# IMU_v2.net
KiCad netlist of a schematic drawn in EAGLE
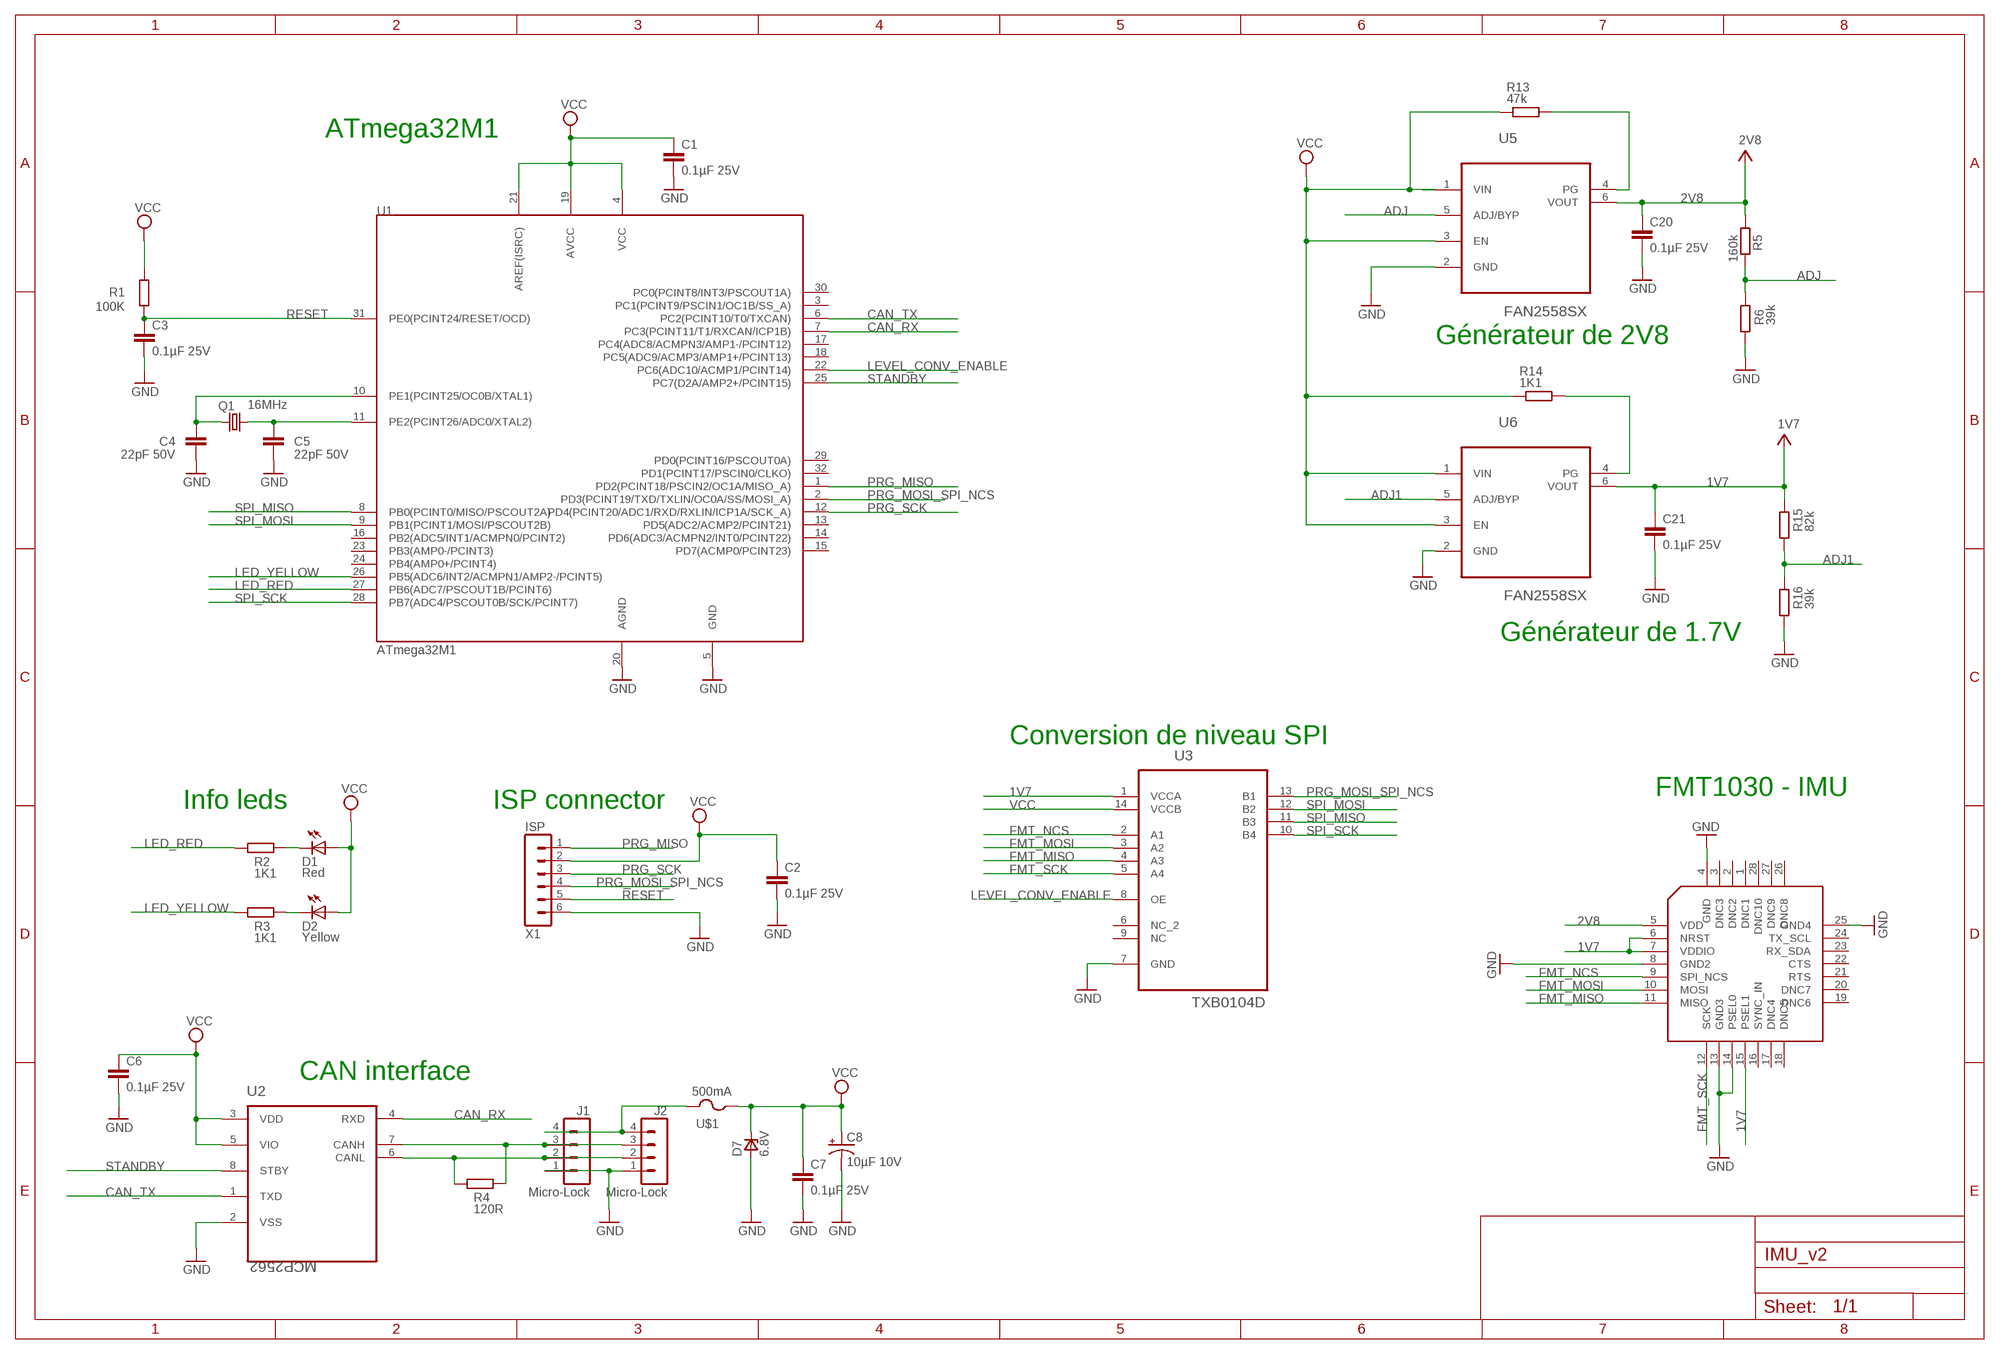
[diagram p0: schematic, sheet 1]

(export (version "E")
  (design (tool "Eeschema 10.0.6"))
  (components
    (comp (ref "C1")
      (value "0.1µF 25V")
      (footprint "eagle-import:C2012")
      (fields (field (name "MANUFACTURER") "AVX") (field (name "MPN") "08053C104KAT2A"))
      (libsource (lib "eagle-import") (part "CAPACITOR_NON_POL-0.1µF-25V(+-10%)(2012)"))
    )
    (comp (ref "C2")
      (value "0.1µF 25V")
      (footprint "eagle-import:C2012")
      (fields (field (name "MANUFACTURER") "AVX") (field (name "MPN") "08053C104KAT2A"))
      (libsource (lib "eagle-import") (part "CAPACITOR_NON_POL-0.1µF-25V(+-10%)(2012)"))
    )
    (comp (ref "C3")
      (value "0.1µF 25V")
      (footprint "eagle-import:C2012")
      (fields (field (name "MANUFACTURER") "AVX") (field (name "MPN") "08053C104KAT2A"))
      (libsource (lib "eagle-import") (part "CAPACITOR_NON_POL-0.1µF-25V(+-10%)(2012)"))
    )
    (comp (ref "C4")
      (value "22pF 50V")
      (footprint "eagle-import:C2012")
      (fields (field (name "MANUFACTURER") "Multicomp") (field (name "MPN") "MC0805N220J500CT"))
      (libsource (lib "eagle-import") (part "CAPACITOR_NON_POL-22PF-50V(+-5%)(2012)"))
    )
    (comp (ref "C5")
      (value "22pF 50V")
      (footprint "eagle-import:C2012")
      (fields (field (name "MANUFACTURER") "Multicomp") (field (name "MPN") "MC0805N220J500CT"))
      (libsource (lib "eagle-import") (part "CAPACITOR_NON_POL-22PF-50V(+-5%)(2012)"))
    )
    (comp (ref "C6")
      (value "0.1µF 25V")
      (footprint "eagle-import:C2012")
      (fields (field (name "MANUFACTURER") "AVX") (field (name "MPN") "08053C104KAT2A"))
      (libsource (lib "eagle-import") (part "CAPACITOR_NON_POL-0.1µF-25V(+-10%)(2012)"))
    )
    (comp (ref "C7")
      (value "0.1µF 25V")
      (footprint "eagle-import:C2012")
      (fields (field (name "MANUFACTURER") "AVX") (field (name "MPN") "08053C104KAT2A"))
      (libsource (lib "eagle-import") (part "CAPACITOR_NON_POL-0.1µF-25V(+-10%)(2012)"))
    )
    (comp (ref "C8")
      (value "10µF 10V")
      (footprint "eagle-import:EIA3216")
      (fields (field (name "MANUFACTURER") "Kemet") (field (name "MPN") "T491A106K010AT"))
      (libsource (lib "eagle-import") (part "CAPACITOR_POL-10µF-10V(+-10%)(3216)"))
    )
    (comp (ref "C20")
      (value "0.1µF 25V")
      (footprint "eagle-import:C2012")
      (fields (field (name "MANUFACTURER") "AVX") (field (name "MPN") "08053C104KAT2A"))
      (libsource (lib "eagle-import") (part "CAPACITOR_NON_POL-0.1µF-25V(+-10%)(2012)"))
    )
    (comp (ref "C21")
      (value "0.1µF 25V")
      (footprint "eagle-import:C2012")
      (fields (field (name "MANUFACTURER") "AVX") (field (name "MPN") "08053C104KAT2A"))
      (libsource (lib "eagle-import") (part "CAPACITOR_NON_POL-0.1µF-25V(+-10%)(2012)"))
    )
    (comp (ref "D1")
      (value "Red")
      (footprint "eagle-import:VLD")
      (fields (field (name "MANUFACTURER") "Vishay") (field (name "MPN") "VLDS1235G"))
      (libsource (lib "eagle-import") (part "LEDVLDS1235G"))
    )
    (comp (ref "D2")
      (value "Yellow")
      (footprint "eagle-import:VLD")
      (fields (field (name "MANUFACTURER") "Vishay") (field (name "MPN") "VLDY1235G"))
      (libsource (lib "eagle-import") (part "LED-VLDY1235G"))
    )
    (comp (ref "D7")
      (value "6.8V")
      (footprint "eagle-import:DO-214AA")
      (fields (field (name "MANUFACTURER") "ON Semiconductor") (field (name "MPN") "P6SMB6.8AT3G"))
      (libsource (lib "eagle-import") (part "ZENER_UNIDIR6.8"))
    )
    (comp (ref "J1")
      (value "Micro-Lock")
      (footprint "eagle-import:504195-0470")
      (fields (field (name "MANUFACTURER") "Molex") (field (name "MPN") "504195-0470"))
      (libsource (lib "eagle-import") (part "MICROLOCK-4CMS"))
    )
    (comp (ref "J2")
      (value "Micro-Lock")
      (footprint "eagle-import:504195-0470")
      (fields (field (name "MANUFACTURER") "Molex") (field (name "MPN") "504195-0470"))
      (libsource (lib "eagle-import") (part "MICROLOCK-4CMS"))
    )
    (comp (ref "Q1")
      (value "16MHz")
      (footprint "eagle-import:SMD_KX7")
      (fields (field (name "MANUFACTURER") "AEL CRYSTALS") (field (name "MPN") "E3SB16.0000F09G11AE"))
      (libsource (lib "eagle-import") (part "CRYSTAL-16MHZ_SMD(3225)"))
    )
    (comp (ref "R1")
      (value "100K")
      (footprint "eagle-import:R2012")
      (fields (field (name "MANUFACTURER") "Multicomp") (field (name "MPN") "MCWR08X1003FTL"))
      (libsource (lib "eagle-import") (part "RESISTOR-100K(+-1%)(2012)"))
    )
    (comp (ref "R2")
      (value "1K1")
      (footprint "eagle-import:R2012")
      (fields (field (name "MANUFACTURER") "Multicomp") (field (name "MPN") "MC0805S8F1101T5E"))
      (libsource (lib "eagle-import") (part "RESISTOR-1K1(+-1%)(2012)"))
    )
    (comp (ref "R3")
      (value "1K1")
      (footprint "eagle-import:R2012")
      (fields (field (name "MANUFACTURER") "Multicomp") (field (name "MPN") "MC0805S8F1101T5E"))
      (libsource (lib "eagle-import") (part "RESISTOR-1K1(+-1%)(2012)"))
    )
    (comp (ref "R4")
      (value "120R")
      (footprint "eagle-import:R2012")
      (fields (field (name "MANUFACTURER") "Multicomp") (field (name "MPN") "MCWR08X1200FTL"))
      (libsource (lib "eagle-import") (part "RESISTOR-120R(+-1%)(2012)"))
    )
    (comp (ref "R5")
      (value "160k")
      (footprint "eagle-import:R2012")
      (fields (field (name "MANUFACTURER") "Multicomp") (field (name "MPN") "MC0805S8F1101T5E"))
      (libsource (lib "eagle-import") (part "RESISTOR-1K1(+-1%)(2012)"))
    )
    (comp (ref "R6")
      (value "39k")
      (footprint "eagle-import:R2012")
      (fields (field (name "MANUFACTURER") "Multicomp") (field (name "MPN") "MC0805S8F1101T5E"))
      (libsource (lib "eagle-import") (part "RESISTOR-1K1(+-1%)(2012)"))
    )
    (comp (ref "R13")
      (value "47k")
      (footprint "eagle-import:R2012")
      (fields (field (name "MANUFACTURER") "Multicomp") (field (name "MPN") "MC0805S8F1101T5E"))
      (libsource (lib "eagle-import") (part "RESISTOR-1K1(+-1%)(2012)"))
    )
    (comp (ref "R14")
      (value "1K1")
      (footprint "eagle-import:R2012")
      (fields (field (name "MANUFACTURER") "Multicomp") (field (name "MPN") "MC0805S8F1101T5E"))
      (libsource (lib "eagle-import") (part "RESISTOR-1K1(+-1%)(2012)"))
    )
    (comp (ref "R15")
      (value "82k")
      (footprint "eagle-import:R2012")
      (fields (field (name "MANUFACTURER") "Multicomp") (field (name "MPN") "MC0805S8F1101T5E"))
      (libsource (lib "eagle-import") (part "RESISTOR-1K1(+-1%)(2012)"))
    )
    (comp (ref "R16")
      (value "39k")
      (footprint "eagle-import:R2012")
      (fields (field (name "MANUFACTURER") "Multicomp") (field (name "MPN") "MC0805S8F1101T5E"))
      (libsource (lib "eagle-import") (part "RESISTOR-1K1(+-1%)(2012)"))
    )
    (comp (ref "U$1")
      (value "500mA")
      (footprint "eagle-import:EIARS-481-2")
      (fields (field (name "MANUFACTURER") "Littlefuse") (field (name "MPN") "0451.500MRL"))
      (libsource (lib "eagle-import") (part "FUSE"))
    )
    (comp (ref "U$2")
      (value "FMT1030")
      (footprint "eagle-import:S28")
      (libsource (lib "eagle-import") (part "FMT1030"))
    )
    (comp (ref "U1")
      (value "ATmega32M1")
      (footprint "eagle-import:TQFP32")
      (fields (field (name "MANUFACTURER") "Atmel") (field (name "MPN") "ATmega32M1-AU"))
      (libsource (lib "eagle-import") (part "ATMEGA32M1-TQFP32"))
    )
    (comp (ref "U2")
      (value "MCP2562")
      (footprint "eagle-import:SOIC8")
      (fields (field (name "MANUFACTURER") "Microchip") (field (name "MPN") "MCP2562-E/SN"))
      (libsource (lib "eagle-import") (part "MCP2562-E/SN-SOIC8"))
    )
    (comp (ref "U3")
      (value "TXB0104D")
      (footprint "eagle-import:SOIC127P600X175-14N")
      (libsource (lib "eagle-import") (part "TXB0104D"))
    )
    (comp (ref "U5")
      (value "FAN2558SX")
      (footprint "eagle-import:SOT95P270X145-6N")
      (libsource (lib "eagle-import") (part "FAN2558SX"))
    )
    (comp (ref "U6")
      (value "FAN2558SX")
      (footprint "eagle-import:SOT95P270X145-6N")
      (libsource (lib "eagle-import") (part "FAN2558SX"))
    )
    (comp (ref "X1")
      (value "ISP")
      (footprint "eagle-import:MINITEK_127_6WAY_SMD")
      (fields (field (name "MANUFACTURER") "Minitek") (field (name "MPN") "20021121-00006C4LF"))
      (libsource (lib "eagle-import") (part "MINITEK_127_6WAYS-SMD"))
    )
  )
  (nets
    (net (code "1") (name "/ADJ") (class "Default")
      (node (ref "R5") (pin "2") (pinfunction "2_2") (pintype "passive"))
      (node (ref "R6") (pin "1") (pinfunction "1_1") (pintype "passive"))
      (node (ref "U5") (pin "5") (pinfunction "ADJ/BYP_5") (pintype "input"))
    )
    (net (code "2") (name "/ADJ1") (class "Default")
      (node (ref "R15") (pin "2") (pinfunction "2_2") (pintype "passive"))
      (node (ref "R16") (pin "1") (pinfunction "1_1") (pintype "passive"))
      (node (ref "U6") (pin "5") (pinfunction "ADJ/BYP_5") (pintype "input"))
    )
    (net (code "3") (name "/CAN_RX") (class "Default")
      (node (ref "U1") (pin "7") (pinfunction "PC3(PCINT11/T1/RXCAN/ICP1B)_7") (pintype "bidirectional"))
      (node (ref "U2") (pin "4") (pinfunction "RXD_4") (pintype "output"))
    )
    (net (code "4") (name "/CAN_TX") (class "Default")
      (node (ref "U1") (pin "6") (pinfunction "PC2(PCINT10/T0/TXCAN)_6") (pintype "bidirectional"))
      (node (ref "U2") (pin "1") (pinfunction "TXD_1") (pintype "input"))
    )
    (net (code "5") (name "/FMT_MISO") (class "Default")
      (node (ref "U$2") (pin "11") (pinfunction "MISO_11") (pintype "bidirectional"))
      (node (ref "U3") (pin "4") (pinfunction "A3_4") (pintype "input"))
    )
    (net (code "6") (name "/FMT_MOSI") (class "Default")
      (node (ref "U$2") (pin "10") (pinfunction "MOSI_10") (pintype "bidirectional"))
      (node (ref "U3") (pin "3") (pinfunction "A2_3") (pintype "input"))
    )
    (net (code "7") (name "/FMT_NCS") (class "Default")
      (node (ref "U$2") (pin "9") (pinfunction "SPI_NCS_9") (pintype "bidirectional"))
      (node (ref "U3") (pin "2") (pinfunction "A1_2") (pintype "input"))
    )
    (net (code "8") (name "/FMT_SCK") (class "Default")
      (node (ref "U$2") (pin "12") (pinfunction "SCK_12") (pintype "bidirectional"))
      (node (ref "U3") (pin "5") (pinfunction "A4_5") (pintype "input"))
    )
    (net (code "9") (name "/LED_RED") (class "Default")
      (node (ref "R2") (pin "2") (pinfunction "2_2") (pintype "passive"))
      (node (ref "U1") (pin "27") (pinfunction "PB6(ADC7/PSCOUT1B/PCINT6)_27") (pintype "bidirectional"))
    )
    (net (code "10") (name "/LED_YELLOW") (class "Default")
      (node (ref "R3") (pin "2") (pinfunction "2_2") (pintype "passive"))
      (node (ref "U1") (pin "26") (pinfunction "PB5(ADC6/INT2/ACMPN1/AMP2-/PCINT5)_26") (pintype "bidirectional"))
    )
    (net (code "11") (name "/LEVEL_CONV_ENABLE") (class "Default")
      (node (ref "U1") (pin "22") (pinfunction "PC6(ADC10/ACMP1/PCINT14)_22") (pintype "bidirectional"))
      (node (ref "U3") (pin "8") (pinfunction "OE_8") (pintype "input"))
    )
    (net (code "12") (name "/PRG_MISO") (class "Default")
      (node (ref "U1") (pin "1") (pinfunction "PD2(PCINT18/PSCIN2/OC1A/MISO_A)_1") (pintype "bidirectional"))
      (node (ref "X1") (pin "1") (pinfunction "1_1") (pintype "passive"))
    )
    (net (code "13") (name "/PRG_MOSI_SPI_NCS") (class "Default")
      (node (ref "U1") (pin "2") (pinfunction "PD3(PCINT19/TXD/TXLIN/OC0A/SS/MOSI_A)_2") (pintype "bidirectional"))
      (node (ref "U3") (pin "13") (pinfunction "B1_13") (pintype "output"))
      (node (ref "X1") (pin "4") (pinfunction "4_4") (pintype "passive"))
    )
    (net (code "14") (name "/PRG_SCK") (class "Default")
      (node (ref "U1") (pin "12") (pinfunction "PD4(PCINT20/ADC1/RXD/RXLIN/ICP1A/SCK_A)_12") (pintype "bidirectional"))
      (node (ref "X1") (pin "3") (pinfunction "3_3") (pintype "passive"))
    )
    (net (code "15") (name "/RESET") (class "Default")
      (node (ref "C3") (pin "1") (pinfunction "1_1") (pintype "passive"))
      (node (ref "R1") (pin "1") (pinfunction "1_1") (pintype "passive"))
      (node (ref "U1") (pin "31") (pinfunction "PE0(PCINT24/RESET/OCD)_31") (pintype "bidirectional"))
      (node (ref "X1") (pin "5") (pinfunction "5_5") (pintype "passive"))
    )
    (net (code "16") (name "/SPI_MISO") (class "Default")
      (node (ref "U1") (pin "8") (pinfunction "PB0(PCINT0/MISO/PSCOUT2A)_8") (pintype "bidirectional"))
      (node (ref "U3") (pin "11") (pinfunction "B3_11") (pintype "output"))
    )
    (net (code "17") (name "/SPI_MOSI") (class "Default")
      (node (ref "U1") (pin "9") (pinfunction "PB1(PCINT1/MOSI/PSCOUT2B)_9") (pintype "bidirectional"))
      (node (ref "U3") (pin "12") (pinfunction "B2_12") (pintype "output"))
    )
    (net (code "18") (name "/SPI_SCK") (class "Default")
      (node (ref "U1") (pin "28") (pinfunction "PB7(ADC4/PSCOUT0B/SCK/PCINT7)_28") (pintype "bidirectional"))
      (node (ref "U3") (pin "10") (pinfunction "B4_10") (pintype "output"))
    )
    (net (code "19") (name "/STANDBY") (class "Default")
      (node (ref "U1") (pin "25") (pinfunction "PC7(D2A/AMP2+/PCINT15)_25") (pintype "bidirectional"))
      (node (ref "U2") (pin "8") (pinfunction "STBY_8") (pintype "input"))
    )
    (net (code "20") (name "1V7") (class "Default")
      (node (ref "C21") (pin "1") (pinfunction "1_1") (pintype "passive"))
      (node (ref "R15") (pin "1") (pinfunction "1_1") (pintype "passive"))
      (node (ref "U$2") (pin "15") (pinfunction "PSEL1_15") (pintype "bidirectional"))
      (node (ref "U$2") (pin "6") (pinfunction "NRST_6") (pintype "bidirectional"))
      (node (ref "U$2") (pin "7") (pinfunction "VDDIO_7") (pintype "bidirectional"))
      (node (ref "U3") (pin "1") (pinfunction "VCCA_1") (pintype "power_in"))
      (node (ref "U6") (pin "6") (pinfunction "VOUT_6") (pintype "output"))
    )
    (net (code "21") (name "2V8") (class "Default")
      (node (ref "C20") (pin "1") (pinfunction "1_1") (pintype "passive"))
      (node (ref "R5") (pin "1") (pinfunction "1_1") (pintype "passive"))
      (node (ref "U$2") (pin "5") (pinfunction "VDD_5") (pintype "bidirectional"))
      (node (ref "U5") (pin "6") (pinfunction "VOUT_6") (pintype "output"))
    )
    (net (code "22") (name "GND") (class "Default")
      (node (ref "C1") (pin "2") (pinfunction "2_2") (pintype "passive"))
      (node (ref "C2") (pin "2") (pinfunction "2_2") (pintype "passive"))
      (node (ref "C20") (pin "2") (pinfunction "2_2") (pintype "passive"))
      (node (ref "C21") (pin "2") (pinfunction "2_2") (pintype "passive"))
      (node (ref "C3") (pin "2") (pinfunction "2_2") (pintype "passive"))
      (node (ref "C4") (pin "2") (pinfunction "2_2") (pintype "passive"))
      (node (ref "C5") (pin "2") (pinfunction "2_2") (pintype "passive"))
      (node (ref "C6") (pin "2") (pinfunction "2_2") (pintype "passive"))
      (node (ref "C7") (pin "2") (pinfunction "2_2") (pintype "passive"))
      (node (ref "C8") (pin "C") (pinfunction "-_C") (pintype "passive"))
      (node (ref "D7") (pin "A") (pinfunction "A_A") (pintype "passive"))
      (node (ref "J1") (pin "1") (pinfunction "1_1") (pintype "passive"))
      (node (ref "J2") (pin "1") (pinfunction "1_1") (pintype "passive"))
      (node (ref "R16") (pin "2") (pinfunction "2_2") (pintype "passive"))
      (node (ref "R6") (pin "2") (pinfunction "2_2") (pintype "passive"))
      (node (ref "U$2") (pin "13") (pinfunction "GND3_13") (pintype "bidirectional"))
      (node (ref "U$2") (pin "14") (pinfunction "PSEL0_14") (pintype "bidirectional"))
      (node (ref "U$2") (pin "25") (pinfunction "GND4_25") (pintype "bidirectional"))
      (node (ref "U$2") (pin "4") (pinfunction "GND_4") (pintype "bidirectional"))
      (node (ref "U$2") (pin "8") (pinfunction "GND2_8") (pintype "bidirectional"))
      (node (ref "U1") (pin "20") (pinfunction "AGND_20") (pintype "power_in"))
      (node (ref "U1") (pin "5") (pinfunction "GND_5") (pintype "power_in"))
      (node (ref "U2") (pin "2") (pinfunction "VSS_2") (pintype "power_in"))
      (node (ref "U3") (pin "7") (pinfunction "GND_7") (pintype "passive"))
      (node (ref "U5") (pin "2") (pinfunction "GND_2") (pintype "passive"))
      (node (ref "U6") (pin "2") (pinfunction "GND_2") (pintype "passive"))
      (node (ref "X1") (pin "6") (pinfunction "6_6") (pintype "passive"))
    )
    (net (code "23") (name "Net-(D1-PadC)") (class "Default")
      (node (ref "D1") (pin "C") (pinfunction "C_C") (pintype "passive"))
      (node (ref "R2") (pin "1") (pinfunction "1_1") (pintype "passive"))
    )
    (net (code "24") (name "Net-(D2-PadC)") (class "Default")
      (node (ref "D2") (pin "C") (pinfunction "C_C") (pintype "passive"))
      (node (ref "R3") (pin "1") (pinfunction "1_1") (pintype "passive"))
    )
    (net (code "25") (name "Net-(J1-Pad4)") (class "Default")
      (node (ref "J1") (pin "4") (pinfunction "4_4") (pintype "passive"))
      (node (ref "J2") (pin "4") (pinfunction "4_4") (pintype "passive"))
      (node (ref "U$1") (pin "2") (pinfunction "2_2") (pintype "passive"))
    )
    (net (code "26") (name "Net-(Q1-2)") (class "Default")
      (node (ref "C5") (pin "1") (pinfunction "1_1") (pintype "passive"))
      (node (ref "Q1") (pin "3") (pinfunction "2_3") (pintype "passive"))
      (node (ref "U1") (pin "11") (pinfunction "PE2(PCINT26/ADC0/XTAL2)_11") (pintype "bidirectional"))
    )
    (net (code "27") (name "Net-(U1-PE1(PCINT25{slash}OC0B{slash}XTAL1))") (class "Default")
      (node (ref "C4") (pin "1") (pinfunction "1_1") (pintype "passive"))
      (node (ref "Q1") (pin "1") (pinfunction "1_1") (pintype "passive"))
      (node (ref "U1") (pin "10") (pinfunction "PE1(PCINT25/OC0B/XTAL1)_10") (pintype "bidirectional"))
    )
    (net (code "28") (name "Net-(U2-CANH)") (class "Default")
      (node (ref "J1") (pin "3") (pinfunction "3_3") (pintype "passive"))
      (node (ref "J2") (pin "3") (pinfunction "3_3") (pintype "passive"))
      (node (ref "R4") (pin "1") (pinfunction "1_1") (pintype "passive"))
      (node (ref "U2") (pin "7") (pinfunction "CANH_7") (pintype "bidirectional"))
    )
    (net (code "29") (name "Net-(U2-CANL)") (class "Default")
      (node (ref "J1") (pin "2") (pinfunction "2_2") (pintype "passive"))
      (node (ref "J2") (pin "2") (pinfunction "2_2") (pintype "passive"))
      (node (ref "R4") (pin "2") (pinfunction "2_2") (pintype "passive"))
      (node (ref "U2") (pin "6") (pinfunction "CANL_6") (pintype "bidirectional"))
    )
    (net (code "30") (name "Net-(U5-PG)") (class "Default")
      (node (ref "R13") (pin "1") (pinfunction "1_1") (pintype "passive"))
      (node (ref "U5") (pin "4") (pinfunction "PG_4") (pintype "output"))
    )
    (net (code "31") (name "Net-(U6-PG)") (class "Default")
      (node (ref "R14") (pin "2") (pinfunction "2_2") (pintype "passive"))
      (node (ref "U6") (pin "4") (pinfunction "PG_4") (pintype "output"))
    )
    (net (code "32") (name "VCC") (class "Default")
      (node (ref "C1") (pin "1") (pinfunction "1_1") (pintype "passive"))
      (node (ref "C2") (pin "1") (pinfunction "1_1") (pintype "passive"))
      (node (ref "C6") (pin "1") (pinfunction "1_1") (pintype "passive"))
      (node (ref "C7") (pin "1") (pinfunction "1_1") (pintype "passive"))
      (node (ref "C8") (pin "A") (pinfunction "+_A") (pintype "passive"))
      (node (ref "D1") (pin "A") (pinfunction "A_A") (pintype "passive"))
      (node (ref "D2") (pin "A") (pinfunction "A_A") (pintype "passive"))
      (node (ref "D7") (pin "C") (pinfunction "C_C") (pintype "passive"))
      (node (ref "R1") (pin "2") (pinfunction "2_2") (pintype "passive"))
      (node (ref "R13") (pin "2") (pinfunction "2_2") (pintype "passive"))
      (node (ref "R14") (pin "1") (pinfunction "1_1") (pintype "passive"))
      (node (ref "U$1") (pin "1") (pinfunction "1_1") (pintype "passive"))
      (node (ref "U1") (pin "19") (pinfunction "AVCC_19") (pintype "power_in"))
      (node (ref "U1") (pin "21") (pinfunction "AREF(ISRC)_21") (pintype "power_in"))
      (node (ref "U1") (pin "4") (pinfunction "VCC_4") (pintype "power_in"))
      (node (ref "U2") (pin "3") (pinfunction "VDD_3") (pintype "power_in"))
      (node (ref "U2") (pin "5") (pinfunction "VIO_5") (pintype "power_in"))
      (node (ref "U3") (pin "14") (pinfunction "VCCB_14") (pintype "power_in"))
      (node (ref "U5") (pin "1") (pinfunction "VIN_1") (pintype "power_in"))
      (node (ref "U5") (pin "3") (pinfunction "EN_3") (pintype "input"))
      (node (ref "U6") (pin "1") (pinfunction "VIN_1") (pintype "power_in"))
      (node (ref "U6") (pin "3") (pinfunction "EN_3") (pintype "input"))
      (node (ref "X1") (pin "2") (pinfunction "2_2") (pintype "passive"))
    )
    (net (code "33") (name "unconnected-(U$2-CTS-Pad22)") (class "Default")
      (node (ref "U$2") (pin "22") (pinfunction "CTS_22") (pintype "bidirectional"))
    )
    (net (code "34") (name "unconnected-(U$2-DNC1-Pad1)") (class "Default")
      (node (ref "U$2") (pin "1") (pinfunction "DNC1_1") (pintype "bidirectional"))
    )
    (net (code "35") (name "unconnected-(U$2-DNC2-Pad2)") (class "Default")
      (node (ref "U$2") (pin "2") (pinfunction "DNC2_2") (pintype "bidirectional"))
    )
    (net (code "36") (name "unconnected-(U$2-DNC3-Pad3)") (class "Default")
      (node (ref "U$2") (pin "3") (pinfunction "DNC3_3") (pintype "bidirectional"))
    )
    (net (code "37") (name "unconnected-(U$2-DNC4-Pad17)") (class "Default")
      (node (ref "U$2") (pin "17") (pinfunction "DNC4_17") (pintype "bidirectional"))
    )
    (net (code "38") (name "unconnected-(U$2-DNC5-Pad18)") (class "Default")
      (node (ref "U$2") (pin "18") (pinfunction "DNC5_18") (pintype "bidirectional"))
    )
    (net (code "39") (name "unconnected-(U$2-DNC6-Pad19)") (class "Default")
      (node (ref "U$2") (pin "19") (pinfunction "DNC6_19") (pintype "bidirectional"))
    )
    (net (code "40") (name "unconnected-(U$2-DNC7-Pad20)") (class "Default")
      (node (ref "U$2") (pin "20") (pinfunction "DNC7_20") (pintype "bidirectional"))
    )
    (net (code "41") (name "unconnected-(U$2-DNC8-Pad26)") (class "Default")
      (node (ref "U$2") (pin "26") (pinfunction "DNC8_26") (pintype "bidirectional"))
    )
    (net (code "42") (name "unconnected-(U$2-DNC9-Pad27)") (class "Default")
      (node (ref "U$2") (pin "27") (pinfunction "DNC9_27") (pintype "bidirectional"))
    )
    (net (code "43") (name "unconnected-(U$2-DNC10-Pad28)") (class "Default")
      (node (ref "U$2") (pin "28") (pinfunction "DNC10_28") (pintype "bidirectional"))
    )
    (net (code "44") (name "unconnected-(U$2-RTS-Pad21)") (class "Default")
      (node (ref "U$2") (pin "21") (pinfunction "RTS_21") (pintype "bidirectional"))
    )
    (net (code "45") (name "unconnected-(U$2-RX_SDA-Pad23)") (class "Default")
      (node (ref "U$2") (pin "23") (pinfunction "RX_SDA_23") (pintype "bidirectional"))
    )
    (net (code "46") (name "unconnected-(U$2-SYNC_IN-Pad16)") (class "Default")
      (node (ref "U$2") (pin "16") (pinfunction "SYNC_IN_16") (pintype "bidirectional"))
    )
    (net (code "47") (name "unconnected-(U$2-TX_SCL-Pad24)") (class "Default")
      (node (ref "U$2") (pin "24") (pinfunction "TX_SCL_24") (pintype "bidirectional"))
    )
    (net (code "48") (name "unconnected-(U1-PB2(ADC5{slash}INT1{slash}ACMPN0{slash}PCINT2)-Pad16)") (class "Default")
      (node (ref "U1") (pin "16") (pinfunction "PB2(ADC5/INT1/ACMPN0/PCINT2)_16") (pintype "bidirectional"))
    )
    (net (code "49") (name "unconnected-(U1-PB3(AMP0-{slash}PCINT3)-Pad23)") (class "Default")
      (node (ref "U1") (pin "23") (pinfunction "PB3(AMP0-/PCINT3)_23") (pintype "bidirectional"))
    )
    (net (code "50") (name "unconnected-(U1-PB4(AMP0+{slash}PCINT4)-Pad24)") (class "Default")
      (node (ref "U1") (pin "24") (pinfunction "PB4(AMP0+/PCINT4)_24") (pintype "bidirectional"))
    )
    (net (code "51") (name "unconnected-(U1-PC0(PCINT8{slash}INT3{slash}PSCOUT1A)-Pad30)") (class "Default")
      (node (ref "U1") (pin "30") (pinfunction "PC0(PCINT8/INT3/PSCOUT1A)_30") (pintype "bidirectional"))
    )
    (net (code "52") (name "unconnected-(U1-PC1(PCINT9{slash}PSCIN1{slash}OC1B{slash}SS_A)-Pad3)") (class "Default")
      (node (ref "U1") (pin "3") (pinfunction "PC1(PCINT9/PSCIN1/OC1B/SS_A)_3") (pintype "bidirectional"))
    )
    (net (code "53") (name "unconnected-(U1-PC4(ADC8{slash}ACMPN3{slash}AMP1-{slash}PCINT12)-Pad17)") (class "Default")
      (node (ref "U1") (pin "17") (pinfunction "PC4(ADC8/ACMPN3/AMP1-/PCINT12)_17") (pintype "bidirectional"))
    )
    (net (code "54") (name "unconnected-(U1-PC5(ADC9{slash}ACMP3{slash}AMP1+{slash}PCINT13)-Pad18)") (class "Default")
      (node (ref "U1") (pin "18") (pinfunction "PC5(ADC9/ACMP3/AMP1+/PCINT13)_18") (pintype "bidirectional"))
    )
    (net (code "55") (name "unconnected-(U1-PD0(PCINT16{slash}PSCOUT0A)-Pad29)") (class "Default")
      (node (ref "U1") (pin "29") (pinfunction "PD0(PCINT16/PSCOUT0A)_29") (pintype "bidirectional"))
    )
    (net (code "56") (name "unconnected-(U1-PD1(PCINT17{slash}PSCIN0{slash}CLKO)-Pad32)") (class "Default")
      (node (ref "U1") (pin "32") (pinfunction "PD1(PCINT17/PSCIN0/CLKO)_32") (pintype "bidirectional"))
    )
    (net (code "57") (name "unconnected-(U1-PD5(ADC2{slash}ACMP2{slash}PCINT21)-Pad13)") (class "Default")
      (node (ref "U1") (pin "13") (pinfunction "PD5(ADC2/ACMP2/PCINT21)_13") (pintype "bidirectional"))
    )
    (net (code "58") (name "unconnected-(U1-PD6(ADC3{slash}ACMPN2{slash}INT0{slash}PCINT22)-Pad14)") (class "Default")
      (node (ref "U1") (pin "14") (pinfunction "PD6(ADC3/ACMPN2/INT0/PCINT22)_14") (pintype "bidirectional"))
    )
    (net (code "59") (name "unconnected-(U1-PD7(ACMP0{slash}PCINT23)-Pad15)") (class "Default")
      (node (ref "U1") (pin "15") (pinfunction "PD7(ACMP0/PCINT23)_15") (pintype "bidirectional"))
    )
    (net (code "60") (name "unconnected-(U3-NC-Pad9)") (class "Default")
      (node (ref "U3") (pin "9") (pinfunction "NC_9") (pintype "input"))
    )
    (net (code "61") (name "unconnected-(U3-NC_2-Pad6)") (class "Default")
      (node (ref "U3") (pin "6") (pinfunction "NC_2_6") (pintype "input"))
    )
  )
)
